# CAN_PHY.net
KiCad netlist of a schematic drawn in Altium Designer
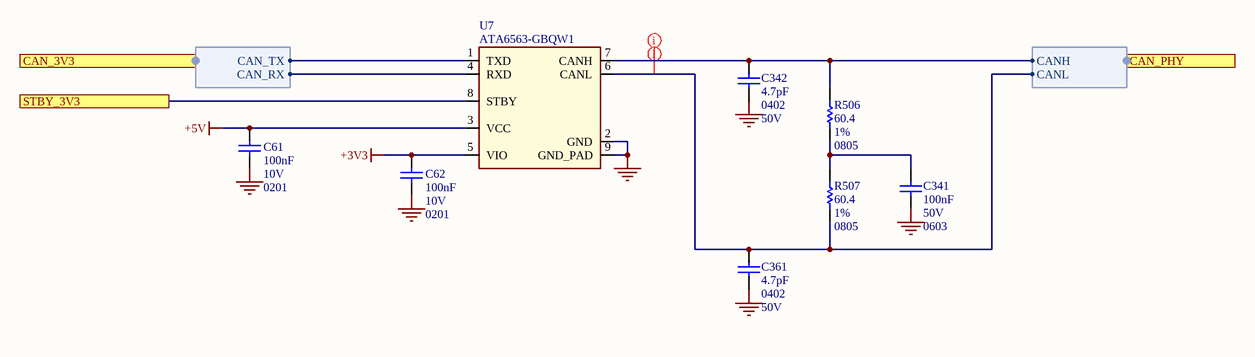
[diagram p0: CAN_PHY.SchDoc]

(export (version "E")
  (design (tool "Eeschema 10.0.6"))
  (components
    (comp (ref "C61")
      (value "100nF")
      (footprint "CAP-0201")
      (description "CAP CHIP 0201 100nF 10% 10V X5R")
      (fields
        (field (name "PART NUMBER") "CL03A104KP3NNNC")
        (field (name "MANUFACTURER") "Samsung Electro-Mechanics")
        (field (name "VOLTAGE") "10V")
        (field (name "CASE CODE (IMPERIAL)") "0201")
      )
      (libsource (lib "Clean") (part "CAP"))
    )
    (comp (ref "C62")
      (value "100nF")
      (footprint "CAP-0201")
      (description "CAP CHIP 0201 100nF 10% 10V X5R")
      (fields
        (field (name "PART NUMBER") "CL03A104KP3NNNC")
        (field (name "MANUFACTURER") "Samsung Electro-Mechanics")
        (field (name "VOLTAGE") "10V")
        (field (name "CASE CODE (IMPERIAL)") "0201")
      )
      (libsource (lib "Clean") (part "CAP"))
    )
    (comp (ref "C341")
      (value "100nF")
      (footprint "CAP-0603")
      (description "CAP CHIP 0603 100nF 10% 50V X7R")
      (fields
        (field (name "MANUFACTURER") "Walsin")
        (field (name "PART NUMBER") "0603B104K500CT")
        (field (name "VOLTAGE") "50V")
        (field (name "CASE CODE (IMPERIAL)") "0603")
      )
      (libsource (lib "Clean") (part "CAP"))
    )
    (comp (ref "C342")
      (value "4.7pF")
      (footprint "CAP-0402")
      (description "CAP CHIP 0402 4.7pF ±0.5pF 50V C0G")
      (fields
        (field (name "CASE CODE (IMPERIAL)") "0402")
        (field (name "PART NUMBER") "04025A4R7DAT2A")
        (field (name "VOLTAGE") "50V")
        (field (name "TOLERANCE") "4.7%")
      )
      (libsource (lib "Clean") (part "CAP"))
    )
    (comp (ref "C361")
      (value "4.7pF")
      (footprint "CAP-0402")
      (description "CAP CHIP 0402 4.7pF ±0.5pF 50V C0G")
      (fields
        (field (name "CASE CODE (IMPERIAL)") "0402")
        (field (name "PART NUMBER") "04025A4R7DAT2A")
        (field (name "VOLTAGE") "50V")
        (field (name "TOLERANCE") "4.7%")
      )
      (libsource (lib "Clean") (part "CAP"))
    )
    (comp (ref "R506")
      (value "60.4")
      (footprint "RES-0805")
      (description "RES CHIP 0805 60R4 1% 1/8W 50ppm")
      (fields
        (field (name "TOLERANCE") "1%")
        (field (name "POWER") "125mW")
        (field (name "PART NUMBER") "RT0805FRE0760R4L")
        (field (name "CASE CODE (IMPERIAL)") "0805")
      )
      (libsource (lib "Clean") (part "RES"))
    )
    (comp (ref "R507")
      (value "60.4")
      (footprint "RES-0805")
      (description "RES CHIP 0805 60R4 1% 1/8W 50ppm")
      (fields
        (field (name "TOLERANCE") "1%")
        (field (name "POWER") "125mW")
        (field (name "PART NUMBER") "RT0805FRE0760R4L")
        (field (name "CASE CODE (IMPERIAL)") "0805")
      )
      (libsource (lib "Clean") (part "RES"))
    )
    (comp (ref "U7")
      (value "ATA6563-GBQW1")
      (footprint "Microchip VDFN8 pitch 0.65mm 3x3mm exposed pad 2.4x1.6mm")
      (description "IC CAN FD PHY 5Mbps, VIO pin, Standby, VDFN8 3x3mm")
      (fields (field (name "MANUFACTURER") "Microchip"))
      (libsource (lib "Clean") (part "ATA6563-GBQW1-Symbol-1"))
    )
  )
  (nets
    (net (code "3") (name "+3V3") (class "Default")
      (node (ref "C62") (pin "2") (pinfunction "2_2") (pintype "passive"))
      (node (ref "U7") (pin "5") (pinfunction "VIO_5") (pintype "passive"))
    )
    (net (code "4") (name "+5V") (class "Default")
      (node (ref "C61") (pin "2") (pinfunction "2_2") (pintype "passive"))
      (node (ref "U7") (pin "3") (pinfunction "VCC_3") (pintype "passive"))
    )
    (net (code "5") (name "/CANH") (class "Default")
      (node (ref "C342") (pin "1") (pinfunction "1_1") (pintype "passive"))
      (node (ref "R506") (pin "2") (pinfunction "2_2") (pintype "passive"))
      (node (ref "U7") (pin "7") (pinfunction "CANH_7") (pintype "passive"))
    )
    (net (code "6") (name "/CANL") (class "Default")
      (node (ref "C361") (pin "1") (pinfunction "1_1") (pintype "passive"))
      (node (ref "R507") (pin "1") (pinfunction "1_1") (pintype "passive"))
      (node (ref "U7") (pin "6") (pinfunction "CANL_6") (pintype "passive"))
    )
    (net (code "7") (name "/CAN_RX") (class "Default")
      (node (ref "U7") (pin "4") (pinfunction "RXD_4") (pintype "passive"))
    )
    (net (code "8") (name "/CAN_TX") (class "Default")
      (node (ref "U7") (pin "1") (pinfunction "TXD_1") (pintype "passive"))
    )
    (net (code "9") (name "/STBY_3V3") (class "Default")
      (node (ref "U7") (pin "8") (pinfunction "STBY_8") (pintype "passive"))
    )
    (net (code "12") (name "GND") (class "Default")
      (node (ref "C341") (pin "2") (pinfunction "2_2") (pintype "passive"))
      (node (ref "C342") (pin "2") (pinfunction "2_2") (pintype "passive"))
      (node (ref "C361") (pin "2") (pinfunction "2_2") (pintype "passive"))
      (node (ref "C61") (pin "1") (pinfunction "1_1") (pintype "passive"))
      (node (ref "C62") (pin "1") (pinfunction "1_1") (pintype "passive"))
      (node (ref "U7") (pin "2") (pinfunction "GND_2") (pintype "passive"))
      (node (ref "U7") (pin "9") (pinfunction "GND_PAD_9") (pintype "passive"))
    )
    (net (code "13") (name "Net-(C341-Pad1)") (class "Default")
      (node (ref "C341") (pin "1") (pinfunction "1_1") (pintype "passive"))
      (node (ref "R506") (pin "1") (pinfunction "1_1") (pintype "passive"))
      (node (ref "R507") (pin "2") (pinfunction "2_2") (pintype "passive"))
    )
  )
)
